# STM32_LQFP64_DEVELOPMENT_BOARD.net
KiCad netlist of a schematic drawn in Altium Designer
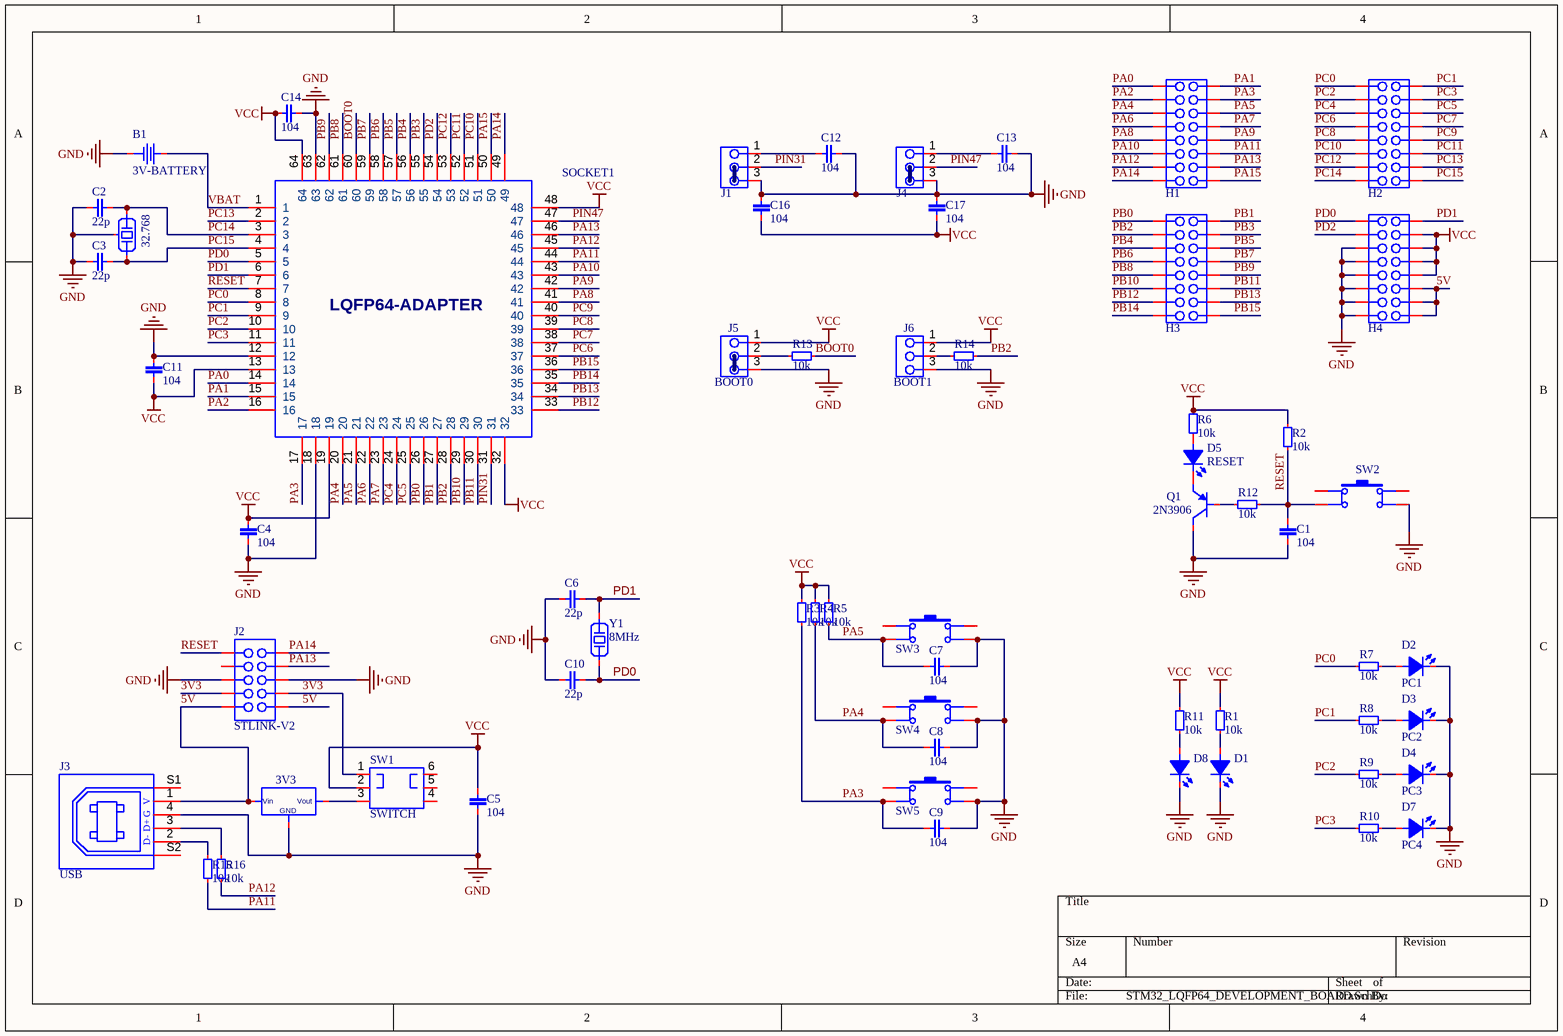
[diagram p0: STM32_LQFP64_DEVELOPMENT_BOARD.SchDoc]

(export (version "E")
  (design (tool "Eeschema 10.0.6"))
  (components
    (comp (ref "B1")
      (value "3V-BATTERY")
      (footprint "CR1220")
      (libsource (lib "MyAltiumLibrary") (part "Batery"))
    )
    (comp (ref "C1") (value "104") (footprint "C0805") (libsource (lib "") (part "Capacitors(SMD)_1")))
    (comp (ref "C2") (value "22p") (footprint "C0805") (libsource (lib "") (part "Capacitors(SMD)_2")))
    (comp (ref "C3") (value "22p") (footprint "C0805") (libsource (lib "") (part "Capacitors(SMD)_2")))
    (comp (ref "C4") (value "104") (footprint "C0805") (libsource (lib "") (part "Capacitors(SMD)_1")))
    (comp (ref "C5") (value "104") (footprint "C1812") (libsource (lib "") (part "Capacitors(SMD)_1")))
    (comp (ref "C6")
      (value "22p")
      (footprint "C0805")
      (libsource (lib "MyAltiumLibrary") (part "Capacitors(SMD)"))
    )
    (comp (ref "C7")
      (value "104")
      (footprint "C0805")
      (libsource (lib "MyAltiumLibrary") (part "Capacitors(SMD)"))
    )
    (comp (ref "C8")
      (value "104")
      (footprint "C0805")
      (libsource (lib "MyAltiumLibrary") (part "Capacitors(SMD)"))
    )
    (comp (ref "C9")
      (value "104")
      (footprint "C0805")
      (libsource (lib "MyAltiumLibrary") (part "Capacitors(SMD)"))
    )
    (comp (ref "C10")
      (value "22p")
      (footprint "C0805")
      (libsource (lib "MyAltiumLibrary") (part "Capacitors(SMD)"))
    )
    (comp (ref "C11") (value "104") (footprint "C0805") (libsource (lib "") (part "Capacitors(SMD)_1")))
    (comp (ref "C12") (value "104") (footprint "C0805") (libsource (lib "") (part "Capacitors(SMD)_2")))
    (comp (ref "C13") (value "104") (footprint "C0805") (libsource (lib "") (part "Capacitors(SMD)_2")))
    (comp (ref "C14") (value "104") (footprint "C0805") (libsource (lib "") (part "Capacitors(SMD)_2")))
    (comp (ref "C16") (value "104") (footprint "C0805") (libsource (lib "") (part "Capacitors(SMD)_3")))
    (comp (ref "C17") (value "104") (footprint "C0805") (libsource (lib "") (part "Capacitors(SMD)_3")))
    (comp (ref "D1")
      (value "LED0805")
      (footprint "L0805RED")
      (libsource (lib "MyAltiumLibrary") (part "LED0805"))
    )
    (comp (ref "D2")
      (value "PC1")
      (footprint "L0805RED")
      (libsource (lib "MyAltiumLibrary") (part "LED0805"))
    )
    (comp (ref "D3")
      (value "PC2")
      (footprint "L0805RED")
      (libsource (lib "MyAltiumLibrary") (part "LED0805"))
    )
    (comp (ref "D4")
      (value "PC3")
      (footprint "L0805RED")
      (libsource (lib "MyAltiumLibrary") (part "LED0805"))
    )
    (comp (ref "D5")
      (value "RESET")
      (footprint "L0805RED")
      (libsource (lib "MyAltiumLibrary") (part "LED0805"))
    )
    (comp (ref "D7")
      (value "PC4")
      (footprint "L0805RED")
      (libsource (lib "MyAltiumLibrary") (part "LED0805"))
    )
    (comp (ref "D8")
      (value "LED0805")
      (footprint "L0805RED")
      (libsource (lib "MyAltiumLibrary") (part "LED0805"))
    )
    (comp (ref "H1")
      (value "HEADER-MALE-DOUBLE")
      (footprint "HEADER-MALE-DOUBLE-16PINS-2.54MM")
      (libsource (lib "MyAltiumLibrary") (part "HEADER-MALE-DOUBLE-16PINS-2.54MM"))
    )
    (comp (ref "H2")
      (value "HEADER-MALE-DOUBLE")
      (footprint "HEADER-MALE-DOUBLE-16PINS-2.54MM")
      (libsource (lib "MyAltiumLibrary") (part "HEADER-MALE-DOUBLE-16PINS-2.54MM"))
    )
    (comp (ref "H3")
      (value "HEADER-MALE-DOUBLE")
      (footprint "HEADER-MALE-DOUBLE-16PINS-2.54MM")
      (libsource (lib "MyAltiumLibrary") (part "HEADER-MALE-DOUBLE-16PINS-2.54MM"))
    )
    (comp (ref "H4")
      (value "HEADER-MALE-DOUBLE")
      (footprint "HEADER-MALE-DOUBLE-16PINS-2.54MM")
      (libsource (lib "MyAltiumLibrary") (part "HEADER-MALE-DOUBLE-16PINS-2.54MM"))
    )
    (comp (ref "J1")
      (value "PIN31")
      (footprint "HEADER-MALE-03PINS-2.54MM")
      (libsource (lib "MyAltiumLibrary") (part "HEADER-MALE-03PINS-2.54MM"))
    )
    (comp (ref "J2")
      (value "STLINK-V2")
      (footprint "IDC_CONNECTOR_10x2.54")
      (libsource (lib "MyAltiumLibrary") (part "IDC_2.54_5x2"))
    )
    (comp (ref "J3")
      (value "USB")
      (footprint "USB-B-TYPE")
      (libsource (lib "MyAltiumLibrary") (part "USB B Type"))
    )
    (comp (ref "J4")
      (value "PIN47")
      (footprint "HEADER-MALE-03PINS-2.54MM")
      (libsource (lib "MyAltiumLibrary") (part "HEADER-MALE-03PINS-2.54MM"))
    )
    (comp (ref "J5")
      (value "BOOT0")
      (footprint "HEADER-MALE-03PINS-2.54MM")
      (libsource (lib "MyAltiumLibrary") (part "HEADER-MALE-03PINS-2.54MM"))
    )
    (comp (ref "J6")
      (value "BOOT1")
      (footprint "HEADER-MALE-03PINS-2.54MM")
      (libsource (lib "MyAltiumLibrary") (part "HEADER-MALE-03PINS-2.54MM"))
    )
    (comp (ref "Q1")
      (value "2N3906")
      (footprint "SOT23-3")
      (libsource (lib "MyAltiumLibrary") (part "Transistor-2N3906 (SOT-23)"))
    )
    (comp (ref "R1")
      (value "10k")
      (footprint "R0805")
      (libsource (lib "MyAltiumLibrary") (part "Resistors-SMD"))
    )
    (comp (ref "R2") (value "10k") (footprint "R0805") (libsource (lib "") (part "Resistors-SMD_3")))
    (comp (ref "R3") (value "10k") (footprint "R0805") (libsource (lib "") (part "Resistors-SMD_3")))
    (comp (ref "R4") (value "10k") (footprint "R0805") (libsource (lib "") (part "Resistors-SMD_3")))
    (comp (ref "R5") (value "10k") (footprint "R0805") (libsource (lib "") (part "Resistors-SMD_3")))
    (comp (ref "R6")
      (value "10k")
      (footprint "R0805")
      (libsource (lib "MyAltiumLibrary") (part "Resistors-SMD"))
    )
    (comp (ref "R7") (value "10k") (footprint "R0805") (libsource (lib "") (part "Resistors-SMD_1")))
    (comp (ref "R8") (value "10k") (footprint "R0805") (libsource (lib "") (part "Resistors-SMD_1")))
    (comp (ref "R9") (value "10k") (footprint "R0805") (libsource (lib "") (part "Resistors-SMD_1")))
    (comp (ref "R10") (value "10k") (footprint "R0805") (libsource (lib "") (part "Resistors-SMD_1")))
    (comp (ref "R11")
      (value "10k")
      (footprint "R0805")
      (libsource (lib "MyAltiumLibrary") (part "Resistors-SMD"))
    )
    (comp (ref "R12") (value "10k") (footprint "R0805") (libsource (lib "") (part "Resistors-SMD_1")))
    (comp (ref "R13") (value "10k") (footprint "R0805") (libsource (lib "") (part "Resistors-SMD_2")))
    (comp (ref "R14") (value "10k") (footprint "R0805") (libsource (lib "") (part "Resistors-SMD_2")))
    (comp (ref "R15")
      (value "10k")
      (footprint "R0805")
      (libsource (lib "MyAltiumLibrary") (part "Resistors-SMD"))
    )
    (comp (ref "R16")
      (value "10k")
      (footprint "R0805")
      (libsource (lib "MyAltiumLibrary") (part "Resistors-SMD"))
    )
    (comp (ref "SOCKET1")
      (value "STM32 MICROCONTROLLER")
      (footprint "SOCKET-ADAPTER-OTQ-64-05-03")
      (libsource (lib "MyAltiumLibrary") (part "Mcu-SOCKET-ADAPTER-OTQ-64-05-03"))
    )
    (comp (ref "SW1")
      (value "SWITCH")
      (footprint "SWITCH 5.8x5.8 6 PINS")
      (libsource (lib "MyAltiumLibrary") (part "SWITCH-DPDT"))
    )
    (comp (ref "SW2")
      (value "RESET")
      (footprint "BUTTON_HOLE_4.3mm")
      (libsource (lib "MyAltiumLibrary") (part "Button Hole"))
    )
    (comp (ref "SW3")
      (value "PG5")
      (footprint "BUTTON_HOLE_4.3mm")
      (libsource (lib "MyAltiumLibrary") (part "Button Hole"))
    )
    (comp (ref "SW4")
      (value "PG6")
      (footprint "BUTTON_HOLE_4.3mm")
      (libsource (lib "MyAltiumLibrary") (part "Button Hole"))
    )
    (comp (ref "SW5")
      (value "PG7")
      (footprint "BUTTON_HOLE_4.3mm")
      (libsource (lib "MyAltiumLibrary") (part "Button Hole"))
    )
    (comp (ref "U1")
      (value "3V3")
      (footprint "SOT223-3")
      (libsource (lib "MyAltiumLibrary") (part "Ic-AMS1117(SOT-223)"))
    )
    (comp (ref "Y1")
      (value "8MHz")
      (footprint "HC-49_THROUGH")
      (libsource (lib "MyAltiumLibrary") (part "Crystal"))
    )
    (comp (ref "Y2")
      (value "32.768")
      (footprint "DT-26")
      (libsource (lib "MyAltiumLibrary") (part "Crystal 32.768KHz"))
    )
  )
  (nets
    (net (code "1") (name "/3V3") (class "Default")
      (node (ref "J2") (pin "7") (pinfunction "7_7") (pintype "passive"))
      (node (ref "J2") (pin "8") (pinfunction "8_8") (pintype "passive"))
      (node (ref "SW1") (pin "1") (pinfunction "1_1") (pintype "passive"))
    )
    (net (code "2") (name "/5V") (class "Default")
      (node (ref "H4") (pin "12") (pinfunction "12_12") (pintype "passive"))
      (node (ref "H4") (pin "14") (pinfunction "14_14") (pintype "passive"))
      (node (ref "H4") (pin "16") (pinfunction "16_16") (pintype "passive"))
      (node (ref "J2") (pin "10") (pinfunction "10_10") (pintype "passive"))
      (node (ref "J2") (pin "9") (pinfunction "9_9") (pintype "passive"))
      (node (ref "J3") (pin "1") (pinfunction "1_1") (pintype "passive"))
      (node (ref "U1") (pin "3") (pinfunction "3_3") (pintype "passive"))
    )
    (net (code "3") (name "/BOOT0") (class "Default")
      (node (ref "R13") (pin "2") (pinfunction "2_2") (pintype "passive"))
      (node (ref "SOCKET1") (pin "60") (pinfunction "60_60") (pintype "passive"))
    )
    (net (code "4") (name "/PA0") (class "Default")
      (node (ref "H1") (pin "1") (pinfunction "1_1") (pintype "passive"))
      (node (ref "SOCKET1") (pin "14") (pinfunction "14_14") (pintype "passive"))
    )
    (net (code "5") (name "/PA1") (class "Default")
      (node (ref "H1") (pin "2") (pinfunction "2_2") (pintype "passive"))
      (node (ref "SOCKET1") (pin "15") (pinfunction "15_15") (pintype "passive"))
    )
    (net (code "6") (name "/PA2") (class "Default")
      (node (ref "H1") (pin "3") (pinfunction "3_3") (pintype "passive"))
      (node (ref "SOCKET1") (pin "16") (pinfunction "16_16") (pintype "passive"))
    )
    (net (code "7") (name "/PA3") (class "Default")
      (node (ref "C9") (pin "1") (pinfunction "1_1") (pintype "passive"))
      (node (ref "H1") (pin "4") (pinfunction "4_4") (pintype "passive"))
      (node (ref "R3") (pin "2") (pinfunction "2_2") (pintype "passive"))
      (node (ref "SOCKET1") (pin "17") (pinfunction "17_17") (pintype "passive"))
      (node (ref "SW5") (pin "2") (pinfunction "2_2") (pintype "passive"))
    )
    (net (code "8") (name "/PA4") (class "Default")
      (node (ref "C8") (pin "1") (pinfunction "1_1") (pintype "passive"))
      (node (ref "H1") (pin "5") (pinfunction "5_5") (pintype "passive"))
      (node (ref "R4") (pin "2") (pinfunction "2_2") (pintype "passive"))
      (node (ref "SOCKET1") (pin "20") (pinfunction "20_20") (pintype "passive"))
      (node (ref "SW4") (pin "2") (pinfunction "2_2") (pintype "passive"))
    )
    (net (code "9") (name "/PA5") (class "Default")
      (node (ref "C7") (pin "1") (pinfunction "1_1") (pintype "passive"))
      (node (ref "H1") (pin "6") (pinfunction "6_6") (pintype "passive"))
      (node (ref "R5") (pin "2") (pinfunction "2_2") (pintype "passive"))
      (node (ref "SOCKET1") (pin "21") (pinfunction "21_21") (pintype "passive"))
      (node (ref "SW3") (pin "2") (pinfunction "2_2") (pintype "passive"))
    )
    (net (code "10") (name "/PA6") (class "Default")
      (node (ref "H1") (pin "7") (pinfunction "7_7") (pintype "passive"))
      (node (ref "SOCKET1") (pin "22") (pinfunction "22_22") (pintype "passive"))
    )
    (net (code "11") (name "/PA7") (class "Default")
      (node (ref "H1") (pin "8") (pinfunction "8_8") (pintype "passive"))
      (node (ref "SOCKET1") (pin "23") (pinfunction "23_23") (pintype "passive"))
    )
    (net (code "12") (name "/PA8") (class "Default")
      (node (ref "H1") (pin "9") (pinfunction "9_9") (pintype "passive"))
      (node (ref "SOCKET1") (pin "41") (pinfunction "41_41") (pintype "passive"))
    )
    (net (code "13") (name "/PA9") (class "Default")
      (node (ref "H1") (pin "10") (pinfunction "10_10") (pintype "passive"))
      (node (ref "SOCKET1") (pin "42") (pinfunction "42_42") (pintype "passive"))
    )
    (net (code "14") (name "/PA10") (class "Default")
      (node (ref "H1") (pin "11") (pinfunction "11_11") (pintype "passive"))
      (node (ref "SOCKET1") (pin "43") (pinfunction "43_43") (pintype "passive"))
    )
    (net (code "15") (name "/PA11") (class "Default")
      (node (ref "H1") (pin "12") (pinfunction "12_12") (pintype "passive"))
      (node (ref "R15") (pin "1") (pinfunction "1_1") (pintype "passive"))
      (node (ref "SOCKET1") (pin "44") (pinfunction "44_44") (pintype "passive"))
    )
    (net (code "16") (name "/PA12") (class "Default")
      (node (ref "H1") (pin "13") (pinfunction "13_13") (pintype "passive"))
      (node (ref "R16") (pin "1") (pinfunction "1_1") (pintype "passive"))
      (node (ref "SOCKET1") (pin "45") (pinfunction "45_45") (pintype "passive"))
    )
    (net (code "17") (name "/PA13") (class "Default")
      (node (ref "H1") (pin "14") (pinfunction "14_14") (pintype "passive"))
      (node (ref "J2") (pin "4") (pinfunction "4_4") (pintype "passive"))
      (node (ref "SOCKET1") (pin "46") (pinfunction "46_46") (pintype "passive"))
    )
    (net (code "18") (name "/PA14") (class "Default")
      (node (ref "H1") (pin "15") (pinfunction "15_15") (pintype "passive"))
      (node (ref "J2") (pin "2") (pinfunction "2_2") (pintype "passive"))
      (node (ref "SOCKET1") (pin "49") (pinfunction "49_49") (pintype "passive"))
    )
    (net (code "19") (name "/PA15") (class "Default")
      (node (ref "H1") (pin "16") (pinfunction "16_16") (pintype "passive"))
      (node (ref "SOCKET1") (pin "50") (pinfunction "50_50") (pintype "passive"))
    )
    (net (code "20") (name "/PB0") (class "Default")
      (node (ref "H3") (pin "1") (pinfunction "1_1") (pintype "passive"))
      (node (ref "SOCKET1") (pin "26") (pinfunction "26_26") (pintype "passive"))
    )
    (net (code "21") (name "/PB1") (class "Default")
      (node (ref "H3") (pin "2") (pinfunction "2_2") (pintype "passive"))
      (node (ref "SOCKET1") (pin "27") (pinfunction "27_27") (pintype "passive"))
    )
    (net (code "22") (name "/PB2") (class "Default")
      (node (ref "H3") (pin "3") (pinfunction "3_3") (pintype "passive"))
      (node (ref "R14") (pin "2") (pinfunction "2_2") (pintype "passive"))
      (node (ref "SOCKET1") (pin "28") (pinfunction "28_28") (pintype "passive"))
    )
    (net (code "23") (name "/PB3") (class "Default")
      (node (ref "H3") (pin "4") (pinfunction "4_4") (pintype "passive"))
      (node (ref "SOCKET1") (pin "55") (pinfunction "55_55") (pintype "passive"))
    )
    (net (code "24") (name "/PB4") (class "Default")
      (node (ref "H3") (pin "5") (pinfunction "5_5") (pintype "passive"))
      (node (ref "SOCKET1") (pin "56") (pinfunction "56_56") (pintype "passive"))
    )
    (net (code "25") (name "/PB5") (class "Default")
      (node (ref "H3") (pin "6") (pinfunction "6_6") (pintype "passive"))
      (node (ref "SOCKET1") (pin "57") (pinfunction "57_57") (pintype "passive"))
    )
    (net (code "26") (name "/PB6") (class "Default")
      (node (ref "H3") (pin "7") (pinfunction "7_7") (pintype "passive"))
      (node (ref "SOCKET1") (pin "58") (pinfunction "58_58") (pintype "passive"))
    )
    (net (code "27") (name "/PB7") (class "Default")
      (node (ref "H3") (pin "8") (pinfunction "8_8") (pintype "passive"))
      (node (ref "SOCKET1") (pin "59") (pinfunction "59_59") (pintype "passive"))
    )
    (net (code "28") (name "/PB8") (class "Default")
      (node (ref "H3") (pin "9") (pinfunction "9_9") (pintype "passive"))
      (node (ref "SOCKET1") (pin "61") (pinfunction "61_61") (pintype "passive"))
    )
    (net (code "29") (name "/PB9") (class "Default")
      (node (ref "H3") (pin "10") (pinfunction "10_10") (pintype "passive"))
      (node (ref "SOCKET1") (pin "62") (pinfunction "62_62") (pintype "passive"))
    )
    (net (code "30") (name "/PB10") (class "Default")
      (node (ref "H3") (pin "11") (pinfunction "11_11") (pintype "passive"))
      (node (ref "SOCKET1") (pin "29") (pinfunction "29_29") (pintype "passive"))
    )
    (net (code "31") (name "/PB11") (class "Default")
      (node (ref "H3") (pin "12") (pinfunction "12_12") (pintype "passive"))
      (node (ref "SOCKET1") (pin "30") (pinfunction "30_30") (pintype "passive"))
    )
    (net (code "32") (name "/PB12") (class "Default")
      (node (ref "H3") (pin "13") (pinfunction "13_13") (pintype "passive"))
      (node (ref "SOCKET1") (pin "33") (pinfunction "33_33") (pintype "passive"))
    )
    (net (code "33") (name "/PB13") (class "Default")
      (node (ref "H3") (pin "14") (pinfunction "14_14") (pintype "passive"))
      (node (ref "SOCKET1") (pin "34") (pinfunction "34_34") (pintype "passive"))
    )
    (net (code "34") (name "/PB14") (class "Default")
      (node (ref "H3") (pin "15") (pinfunction "15_15") (pintype "passive"))
      (node (ref "SOCKET1") (pin "35") (pinfunction "35_35") (pintype "passive"))
    )
    (net (code "35") (name "/PB15") (class "Default")
      (node (ref "H3") (pin "16") (pinfunction "16_16") (pintype "passive"))
      (node (ref "SOCKET1") (pin "36") (pinfunction "36_36") (pintype "passive"))
    )
    (net (code "36") (name "/PC0") (class "Default")
      (node (ref "H2") (pin "1") (pinfunction "1_1") (pintype "passive"))
      (node (ref "R7") (pin "2") (pinfunction "2_2") (pintype "passive"))
      (node (ref "SOCKET1") (pin "8") (pinfunction "8_8") (pintype "passive"))
    )
    (net (code "37") (name "/PC1") (class "Default")
      (node (ref "H2") (pin "2") (pinfunction "2_2") (pintype "passive"))
      (node (ref "R8") (pin "2") (pinfunction "2_2") (pintype "passive"))
      (node (ref "SOCKET1") (pin "9") (pinfunction "9_9") (pintype "passive"))
    )
    (net (code "38") (name "/PC2") (class "Default")
      (node (ref "H2") (pin "3") (pinfunction "3_3") (pintype "passive"))
      (node (ref "R9") (pin "2") (pinfunction "2_2") (pintype "passive"))
      (node (ref "SOCKET1") (pin "10") (pinfunction "10_10") (pintype "passive"))
    )
    (net (code "39") (name "/PC3") (class "Default")
      (node (ref "H2") (pin "4") (pinfunction "4_4") (pintype "passive"))
      (node (ref "R10") (pin "2") (pinfunction "2_2") (pintype "passive"))
      (node (ref "SOCKET1") (pin "11") (pinfunction "11_11") (pintype "passive"))
    )
    (net (code "40") (name "/PC4") (class "Default")
      (node (ref "H2") (pin "5") (pinfunction "5_5") (pintype "passive"))
      (node (ref "SOCKET1") (pin "24") (pinfunction "24_24") (pintype "passive"))
    )
    (net (code "41") (name "/PC5") (class "Default")
      (node (ref "H2") (pin "6") (pinfunction "6_6") (pintype "passive"))
      (node (ref "SOCKET1") (pin "25") (pinfunction "25_25") (pintype "passive"))
    )
    (net (code "42") (name "/PC6") (class "Default")
      (node (ref "H2") (pin "7") (pinfunction "7_7") (pintype "passive"))
      (node (ref "SOCKET1") (pin "37") (pinfunction "37_37") (pintype "passive"))
    )
    (net (code "43") (name "/PC7") (class "Default")
      (node (ref "H2") (pin "8") (pinfunction "8_8") (pintype "passive"))
      (node (ref "SOCKET1") (pin "38") (pinfunction "38_38") (pintype "passive"))
    )
    (net (code "44") (name "/PC8") (class "Default")
      (node (ref "H2") (pin "9") (pinfunction "9_9") (pintype "passive"))
      (node (ref "SOCKET1") (pin "39") (pinfunction "39_39") (pintype "passive"))
    )
    (net (code "45") (name "/PC9") (class "Default")
      (node (ref "H2") (pin "10") (pinfunction "10_10") (pintype "passive"))
      (node (ref "SOCKET1") (pin "40") (pinfunction "40_40") (pintype "passive"))
    )
    (net (code "46") (name "/PC10") (class "Default")
      (node (ref "H2") (pin "11") (pinfunction "11_11") (pintype "passive"))
      (node (ref "SOCKET1") (pin "51") (pinfunction "51_51") (pintype "passive"))
    )
    (net (code "47") (name "/PC11") (class "Default")
      (node (ref "H2") (pin "12") (pinfunction "12_12") (pintype "passive"))
      (node (ref "SOCKET1") (pin "52") (pinfunction "52_52") (pintype "passive"))
    )
    (net (code "48") (name "/PC12") (class "Default")
      (node (ref "H2") (pin "13") (pinfunction "13_13") (pintype "passive"))
      (node (ref "SOCKET1") (pin "53") (pinfunction "53_53") (pintype "passive"))
    )
    (net (code "49") (name "/PC13") (class "Default")
      (node (ref "H2") (pin "14") (pinfunction "14_14") (pintype "passive"))
      (node (ref "SOCKET1") (pin "2") (pinfunction "2_2") (pintype "passive"))
    )
    (net (code "50") (name "/PC14") (class "Default")
      (node (ref "C2") (pin "1") (pinfunction "1_1") (pintype "passive"))
      (node (ref "H2") (pin "15") (pinfunction "15_15") (pintype "passive"))
      (node (ref "SOCKET1") (pin "3") (pinfunction "3_3") (pintype "passive"))
      (node (ref "Y2") (pin "2") (pinfunction "2_2") (pintype "passive"))
    )
    (net (code "51") (name "/PC15") (class "Default")
      (node (ref "C3") (pin "1") (pinfunction "1_1") (pintype "passive"))
      (node (ref "H2") (pin "16") (pinfunction "16_16") (pintype "passive"))
      (node (ref "SOCKET1") (pin "4") (pinfunction "4_4") (pintype "passive"))
      (node (ref "Y2") (pin "1") (pinfunction "1_1") (pintype "passive"))
    )
    (net (code "52") (name "/PD0") (class "Default")
      (node (ref "C10") (pin "2") (pinfunction "2_2") (pintype "passive"))
      (node (ref "H4") (pin "1") (pinfunction "1_1") (pintype "passive"))
      (node (ref "SOCKET1") (pin "5") (pinfunction "5_5") (pintype "passive"))
      (node (ref "Y1") (pin "2") (pinfunction "2_2") (pintype "passive"))
    )
    (net (code "53") (name "/PD1") (class "Default")
      (node (ref "C6") (pin "2") (pinfunction "2_2") (pintype "passive"))
      (node (ref "H4") (pin "2") (pinfunction "2_2") (pintype "passive"))
      (node (ref "SOCKET1") (pin "6") (pinfunction "6_6") (pintype "passive"))
      (node (ref "Y1") (pin "1") (pinfunction "1_1") (pintype "passive"))
    )
    (net (code "54") (name "/PD2") (class "Default")
      (node (ref "H4") (pin "3") (pinfunction "3_3") (pintype "passive"))
      (node (ref "SOCKET1") (pin "54") (pinfunction "54_54") (pintype "passive"))
    )
    (net (code "55") (name "/PIN31") (class "Default")
      (node (ref "J1") (pin "2") (pinfunction "2_2") (pintype "passive"))
      (node (ref "SOCKET1") (pin "31") (pinfunction "31_31") (pintype "passive"))
    )
    (net (code "56") (name "/PIN47") (class "Default")
      (node (ref "J4") (pin "2") (pinfunction "2_2") (pintype "passive"))
      (node (ref "SOCKET1") (pin "47") (pinfunction "47_47") (pintype "passive"))
    )
    (net (code "57") (name "/RESET") (class "Default")
      (node (ref "C1") (pin "2") (pinfunction "2_2") (pintype "passive"))
      (node (ref "J2") (pin "1") (pinfunction "1_1") (pintype "passive"))
      (node (ref "R12") (pin "1") (pinfunction "1_1") (pintype "passive"))
      (node (ref "R2") (pin "2") (pinfunction "2_2") (pintype "passive"))
      (node (ref "SOCKET1") (pin "7") (pinfunction "7_7") (pintype "passive"))
      (node (ref "SW2") (pin "2") (pinfunction "2_2") (pintype "passive"))
    )
    (net (code "58") (name "/VBAT") (class "Default")
      (node (ref "B1") (pin "1") (pinfunction "1_1") (pintype "passive"))
      (node (ref "SOCKET1") (pin "1") (pinfunction "1_1") (pintype "passive"))
    )
    (net (code "59") (name "GND") (class "Default")
      (node (ref "B1") (pin "2") (pinfunction "2_2") (pintype "passive"))
      (node (ref "C1") (pin "1") (pinfunction "1_1") (pintype "passive"))
      (node (ref "C10") (pin "1") (pinfunction "1_1") (pintype "passive"))
      (node (ref "C11") (pin "2") (pinfunction "2_2") (pintype "passive"))
      (node (ref "C12") (pin "1") (pinfunction "1_1") (pintype "passive"))
      (node (ref "C13") (pin "1") (pinfunction "1_1") (pintype "passive"))
      (node (ref "C14") (pin "1") (pinfunction "1_1") (pintype "passive"))
      (node (ref "C16") (pin "1") (pinfunction "1_1") (pintype "passive"))
      (node (ref "C17") (pin "1") (pinfunction "1_1") (pintype "passive"))
      (node (ref "C2") (pin "2") (pinfunction "2_2") (pintype "passive"))
      (node (ref "C3") (pin "2") (pinfunction "2_2") (pintype "passive"))
      (node (ref "C4") (pin "1") (pinfunction "1_1") (pintype "passive"))
      (node (ref "C5") (pin "1") (pinfunction "1_1") (pintype "passive"))
      (node (ref "C6") (pin "1") (pinfunction "1_1") (pintype "passive"))
      (node (ref "C7") (pin "2") (pinfunction "2_2") (pintype "passive"))
      (node (ref "C8") (pin "2") (pinfunction "2_2") (pintype "passive"))
      (node (ref "C9") (pin "2") (pinfunction "2_2") (pintype "passive"))
      (node (ref "D1") (pin "2") (pinfunction "K_2") (pintype "passive"))
      (node (ref "D2") (pin "2") (pinfunction "K_2") (pintype "passive"))
      (node (ref "D3") (pin "2") (pinfunction "K_2") (pintype "passive"))
      (node (ref "D4") (pin "2") (pinfunction "K_2") (pintype "passive"))
      (node (ref "D7") (pin "2") (pinfunction "K_2") (pintype "passive"))
      (node (ref "D8") (pin "2") (pinfunction "K_2") (pintype "passive"))
      (node (ref "H4") (pin "11") (pinfunction "11_11") (pintype "passive"))
      (node (ref "H4") (pin "13") (pinfunction "13_13") (pintype "passive"))
      (node (ref "H4") (pin "15") (pinfunction "15_15") (pintype "passive"))
      (node (ref "H4") (pin "5") (pinfunction "5_5") (pintype "passive"))
      (node (ref "H4") (pin "7") (pinfunction "7_7") (pintype "passive"))
      (node (ref "H4") (pin "9") (pinfunction "9_9") (pintype "passive"))
      (node (ref "J1") (pin "3") (pinfunction "3_3") (pintype "passive"))
      (node (ref "J2") (pin "5") (pinfunction "5_5") (pintype "passive"))
      (node (ref "J2") (pin "6") (pinfunction "6_6") (pintype "passive"))
      (node (ref "J3") (pin "4") (pinfunction "4_4") (pintype "passive"))
      (node (ref "J4") (pin "3") (pinfunction "3_3") (pintype "passive"))
      (node (ref "J5") (pin "3") (pinfunction "3_3") (pintype "passive"))
      (node (ref "J6") (pin "3") (pinfunction "3_3") (pintype "passive"))
      (node (ref "Q1") (pin "3") (pinfunction "C_3") (pintype "passive"))
      (node (ref "SOCKET1") (pin "12") (pinfunction "12_12") (pintype "passive"))
      (node (ref "SOCKET1") (pin "18") (pinfunction "18_18") (pintype "passive"))
      (node (ref "SOCKET1") (pin "63") (pinfunction "63_63") (pintype "passive"))
      (node (ref "SW2") (pin "4") (pinfunction "4_4") (pintype "passive"))
      (node (ref "SW3") (pin "4") (pinfunction "4_4") (pintype "passive"))
      (node (ref "SW4") (pin "4") (pinfunction "4_4") (pintype "passive"))
      (node (ref "SW5") (pin "4") (pinfunction "4_4") (pintype "passive"))
      (node (ref "U1") (pin "1") (pinfunction "1_1") (pintype "passive"))
      (node (ref "Y2") (pin "3") (pinfunction "GND_3") (pintype "passive"))
    )
    (net (code "60") (name "Net-(C12-Pad2)") (class "Default")
      (node (ref "C12") (pin "2") (pinfunction "2_2") (pintype "passive"))
      (node (ref "J1") (pin "1") (pinfunction "1_1") (pintype "passive"))
    )
    (net (code "61") (name "Net-(C13-Pad2)") (class "Default")
      (node (ref "C13") (pin "2") (pinfunction "2_2") (pintype "passive"))
      (node (ref "J4") (pin "1") (pinfunction "1_1") (pintype "passive"))
    )
    (net (code "62") (name "Net-(D1-A)") (class "Default")
      (node (ref "D1") (pin "1") (pinfunction "A_1") (pintype "passive"))
      (node (ref "R1") (pin "1") (pinfunction "1_1") (pintype "passive"))
    )
    (net (code "63") (name "Net-(D2-A)") (class "Default")
      (node (ref "D2") (pin "1") (pinfunction "A_1") (pintype "passive"))
      (node (ref "R7") (pin "1") (pinfunction "1_1") (pintype "passive"))
    )
    (net (code "64") (name "Net-(D3-A)") (class "Default")
      (node (ref "D3") (pin "1") (pinfunction "A_1") (pintype "passive"))
      (node (ref "R8") (pin "1") (pinfunction "1_1") (pintype "passive"))
    )
    (net (code "65") (name "Net-(D4-A)") (class "Default")
      (node (ref "D4") (pin "1") (pinfunction "A_1") (pintype "passive"))
      (node (ref "R9") (pin "1") (pinfunction "1_1") (pintype "passive"))
    )
    (net (code "66") (name "Net-(D5-A)") (class "Default")
      (node (ref "D5") (pin "1") (pinfunction "A_1") (pintype "passive"))
      (node (ref "R6") (pin "1") (pinfunction "1_1") (pintype "passive"))
    )
    (net (code "67") (name "Net-(D5-K)") (class "Default")
      (node (ref "D5") (pin "2") (pinfunction "K_2") (pintype "passive"))
      (node (ref "Q1") (pin "2") (pinfunction "E_2") (pintype "passive"))
    )
    (net (code "68") (name "Net-(D7-A)") (class "Default")
      (node (ref "D7") (pin "1") (pinfunction "A_1") (pintype "passive"))
      (node (ref "R10") (pin "1") (pinfunction "1_1") (pintype "passive"))
    )
    (net (code "69") (name "Net-(D8-A)") (class "Default")
      (node (ref "D8") (pin "1") (pinfunction "A_1") (pintype "passive"))
      (node (ref "R11") (pin "1") (pinfunction "1_1") (pintype "passive"))
    )
    (net (code "70") (name "Net-(J3-Pad2)") (class "Default")
      (node (ref "J3") (pin "2") (pinfunction "2_2") (pintype "passive"))
      (node (ref "R15") (pin "2") (pinfunction "2_2") (pintype "passive"))
    )
    (net (code "71") (name "Net-(J3-Pad3)") (class "Default")
      (node (ref "J3") (pin "3") (pinfunction "3_3") (pintype "passive"))
      (node (ref "R16") (pin "2") (pinfunction "2_2") (pintype "passive"))
    )
    (net (code "72") (name "Net-(J5-Pad2)") (class "Default")
      (node (ref "J5") (pin "2") (pinfunction "2_2") (pintype "passive"))
      (node (ref "R13") (pin "1") (pinfunction "1_1") (pintype "passive"))
    )
    (net (code "73") (name "Net-(J6-Pad2)") (class "Default")
      (node (ref "J6") (pin "2") (pinfunction "2_2") (pintype "passive"))
      (node (ref "R14") (pin "1") (pinfunction "1_1") (pintype "passive"))
    )
    (net (code "74") (name "Net-(Q1-B)") (class "Default")
      (node (ref "Q1") (pin "1") (pinfunction "B_1") (pintype "passive"))
      (node (ref "R12") (pin "2") (pinfunction "2_2") (pintype "passive"))
    )
    (net (code "75") (name "Net-(SW1-Pad3)") (class "Default")
      (node (ref "SW1") (pin "3") (pinfunction "3_3") (pintype "passive"))
      (node (ref "U1") (pin "2") (pinfunction "2_2") (pintype "passive"))
    )
    (net (code "76") (name "VCC") (class "Default")
      (node (ref "C11") (pin "1") (pinfunction "1_1") (pintype "passive"))
      (node (ref "C14") (pin "2") (pinfunction "2_2") (pintype "passive"))
      (node (ref "C16") (pin "2") (pinfunction "2_2") (pintype "passive"))
      (node (ref "C17") (pin "2") (pinfunction "2_2") (pintype "passive"))
      (node (ref "C4") (pin "2") (pinfunction "2_2") (pintype "passive"))
      (node (ref "C5") (pin "2") (pinfunction "2_2") (pintype "passive"))
      (node (ref "H4") (pin "10") (pinfunction "10_10") (pintype "passive"))
      (node (ref "H4") (pin "4") (pinfunction "4_4") (pintype "passive"))
      (node (ref "H4") (pin "6") (pinfunction "6_6") (pintype "passive"))
      (node (ref "H4") (pin "8") (pinfunction "8_8") (pintype "passive"))
      (node (ref "J5") (pin "1") (pinfunction "1_1") (pintype "passive"))
      (node (ref "J6") (pin "1") (pinfunction "1_1") (pintype "passive"))
      (node (ref "R1") (pin "2") (pinfunction "2_2") (pintype "passive"))
      (node (ref "R11") (pin "2") (pinfunction "2_2") (pintype "passive"))
      (node (ref "R2") (pin "1") (pinfunction "1_1") (pintype "passive"))
      (node (ref "R3") (pin "1") (pinfunction "1_1") (pintype "passive"))
      (node (ref "R4") (pin "1") (pinfunction "1_1") (pintype "passive"))
      (node (ref "R5") (pin "1") (pinfunction "1_1") (pintype "passive"))
      (node (ref "R6") (pin "2") (pinfunction "2_2") (pintype "passive"))
      (node (ref "SOCKET1") (pin "13") (pinfunction "13_13") (pintype "passive"))
      (node (ref "SOCKET1") (pin "19") (pinfunction "19_19") (pintype "passive"))
      (node (ref "SOCKET1") (pin "32") (pinfunction "32_32") (pintype "passive"))
      (node (ref "SOCKET1") (pin "48") (pinfunction "48_48") (pintype "passive"))
      (node (ref "SOCKET1") (pin "64") (pinfunction "64_64") (pintype "passive"))
      (node (ref "SW1") (pin "2") (pinfunction "2_2") (pintype "passive"))
    )
    (net (code "77") (name "unconnected-(J2-Pad3)") (class "Default")
      (node (ref "J2") (pin "3") (pinfunction "3_3") (pintype "passive"))
    )
    (net (code "78") (name "unconnected-(J3-PadS1)") (class "Default")
      (node (ref "J3") (pin "S1") (pinfunction "S1_S1") (pintype "passive"))
    )
    (net (code "79") (name "unconnected-(J3-PadS2)") (class "Default")
      (node (ref "J3") (pin "S2") (pinfunction "S2_S2") (pintype "passive"))
    )
    (net (code "80") (name "unconnected-(SW1-Pad4)") (class "Default")
      (node (ref "SW1") (pin "4") (pinfunction "4_4") (pintype "passive"))
    )
    (net (code "81") (name "unconnected-(SW1-Pad5)") (class "Default")
      (node (ref "SW1") (pin "5") (pinfunction "5_5") (pintype "passive"))
    )
    (net (code "82") (name "unconnected-(SW1-Pad6)") (class "Default")
      (node (ref "SW1") (pin "6") (pinfunction "6_6") (pintype "passive"))
    )
    (net (code "83") (name "unconnected-(SW2-Pad1)") (class "Default")
      (node (ref "SW2") (pin "1") (pinfunction "1_1") (pintype "passive"))
    )
    (net (code "84") (name "unconnected-(SW2-Pad3)") (class "Default")
      (node (ref "SW2") (pin "3") (pinfunction "3_3") (pintype "passive"))
    )
    (net (code "85") (name "unconnected-(SW3-Pad1)") (class "Default")
      (node (ref "SW3") (pin "1") (pinfunction "1_1") (pintype "passive"))
    )
    (net (code "86") (name "unconnected-(SW3-Pad3)") (class "Default")
      (node (ref "SW3") (pin "3") (pinfunction "3_3") (pintype "passive"))
    )
    (net (code "87") (name "unconnected-(SW4-Pad1)") (class "Default")
      (node (ref "SW4") (pin "1") (pinfunction "1_1") (pintype "passive"))
    )
    (net (code "88") (name "unconnected-(SW4-Pad3)") (class "Default")
      (node (ref "SW4") (pin "3") (pinfunction "3_3") (pintype "passive"))
    )
    (net (code "89") (name "unconnected-(SW5-Pad1)") (class "Default")
      (node (ref "SW5") (pin "1") (pinfunction "1_1") (pintype "passive"))
    )
    (net (code "90") (name "unconnected-(SW5-Pad3)") (class "Default")
      (node (ref "SW5") (pin "3") (pinfunction "3_3") (pintype "passive"))
    )
  )
)
